# Power_Supply.net
KiCad netlist of a schematic drawn in Altium Designer
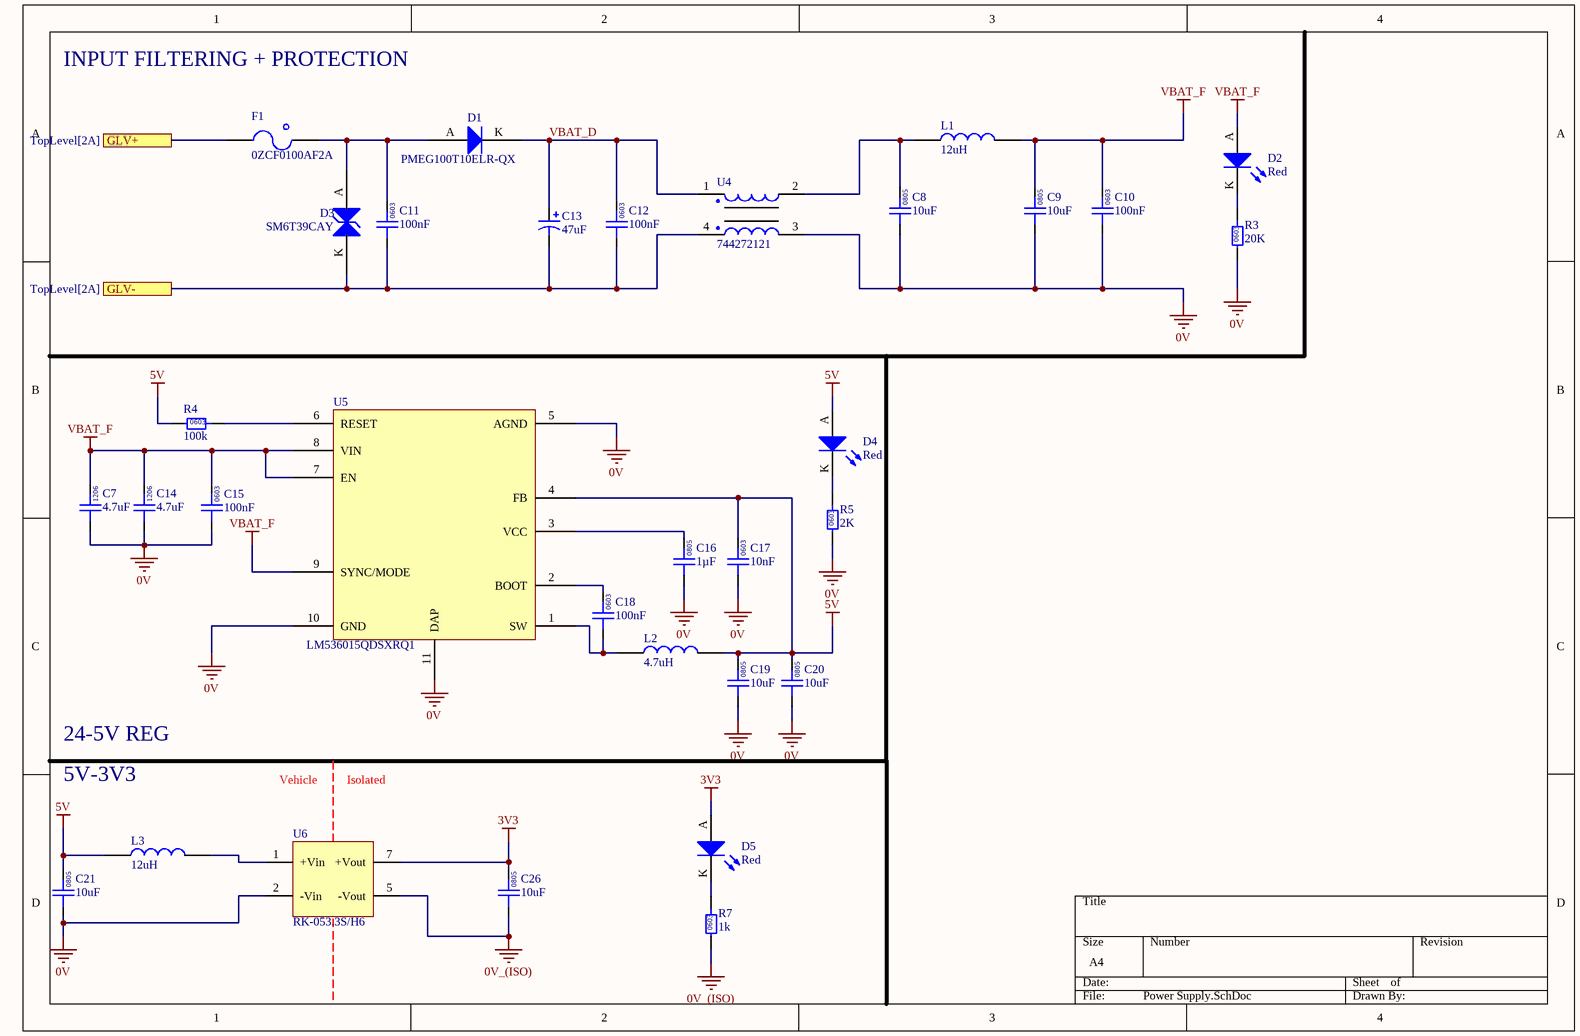
[diagram p0: Power Supply.SchDoc]

(export (version "E")
  (design (tool "Eeschema 10.0.6"))
  (components
    (comp (ref "C7")
      (value "4.7uF")
      (footprint "1206 CAP")
      (fields
        (field (name "PART NUMBER") "GRM31CR71H475KA12K")
        (field (name "MANUFACTURER") "Murata Electronics")
        (field (name "TOLERANCE") "±10%")
      )
      (libsource (lib "ts_standard_library") (part "Capacitor 1206"))
    )
    (comp (ref "C8")
      (value "10uF")
      (footprint "0805")
      (fields
        (field (name "PART NUMBER") "GRM21BR6YA106KE43L")
        (field (name "MANUFACTURER") "muRata")
        (field (name "TOLERANCE") "10%")
      )
      (libsource (lib "ts_standard_library") (part "Capacitor 0805"))
    )
    (comp (ref "C9")
      (value "10uF")
      (footprint "0805")
      (fields
        (field (name "PART NUMBER") "GRM21BR6YA106KE43L")
        (field (name "MANUFACTURER") "muRata")
        (field (name "TOLERANCE") "10%")
      )
      (libsource (lib "ts_standard_library") (part "Capacitor 0805"))
    )
    (comp (ref "C10")
      (value "100nF")
      (footprint "0603")
      (fields
        (field (name "PART NUMBER") "GCM188L81H104KA57D")
        (field (name "MANUFACTURER") "muRata")
        (field (name "TOLERANCE") "±10%")
      )
      (libsource (lib "ts_standard_library") (part "Capacitor 0603"))
    )
    (comp (ref "C11")
      (value "100nF")
      (footprint "0603")
      (fields
        (field (name "PART NUMBER") "GCM188L81H104KA57D")
        (field (name "MANUFACTURER") "muRata")
        (field (name "TOLERANCE") "±10%")
      )
      (libsource (lib "ts_standard_library") (part "Capacitor 0603"))
    )
    (comp (ref "C12")
      (value "100nF")
      (footprint "0603")
      (fields
        (field (name "PART NUMBER") "GCM188L81H104KA57D")
        (field (name "MANUFACTURER") "muRata")
        (field (name "TOLERANCE") "±10%")
      )
      (libsource (lib "ts_standard_library") (part "Capacitor 0603"))
    )
    (comp (ref "C13")
      (value "47uF")
      (footprint "CHEMI-CON ELCO")
      (fields (field (name "PART NUMBER") "HHXA350ARA470MF61G"))
      (libsource (lib "ts_standard_library") (part "Capacitor (Polarised)"))
    )
    (comp (ref "C14")
      (value "4.7uF")
      (footprint "1206 CAP")
      (fields
        (field (name "PART NUMBER") "GRM31CR71H475KA12K")
        (field (name "MANUFACTURER") "Murata Electronics")
        (field (name "TOLERANCE") "±10%")
      )
      (libsource (lib "ts_standard_library") (part "Capacitor 1206"))
    )
    (comp (ref "C15")
      (value "100nF")
      (footprint "0603")
      (fields
        (field (name "PART NUMBER") "GCM188L81H104KA57D")
        (field (name "MANUFACTURER") "muRata")
        (field (name "TOLERANCE") "±10%")
      )
      (libsource (lib "ts_standard_library") (part "Capacitor 0603"))
    )
    (comp (ref "C16")
      (value "1µF")
      (footprint "0805")
      (fields
        (field (name "PART NUMBER") "GCM21BR71H105KA03L")
        (field (name "MANUFACTURER") "muRata")
        (field (name "TOLERANCE") "±10%")
      )
      (libsource (lib "ts_standard_library") (part "Capacitor 0805"))
    )
    (comp (ref "C17")
      (value "10nF")
      (footprint "0603")
      (fields
        (field (name "PART NUMBER") "GCM188L81H103KA03D")
        (field (name "MANUFACTURER") "muRata")
        (field (name "TOLERANCE") "±10%")
      )
      (libsource (lib "ts_standard_library") (part "Capacitor 0603"))
    )
    (comp (ref "C18")
      (value "100nF")
      (footprint "0603")
      (fields
        (field (name "PART NUMBER") "GCM188L81H104KA57D")
        (field (name "MANUFACTURER") "muRata")
        (field (name "TOLERANCE") "±10%")
      )
      (libsource (lib "ts_standard_library") (part "Capacitor 0603"))
    )
    (comp (ref "C19")
      (value "10uF")
      (footprint "0805")
      (fields
        (field (name "PART NUMBER") "GRM21BR6YA106KE43L")
        (field (name "MANUFACTURER") "muRata")
        (field (name "TOLERANCE") "10%")
      )
      (libsource (lib "ts_standard_library") (part "Capacitor 0805"))
    )
    (comp (ref "C20")
      (value "10uF")
      (footprint "0805")
      (fields
        (field (name "PART NUMBER") "GRM21BR6YA106KE43L")
        (field (name "MANUFACTURER") "muRata")
        (field (name "TOLERANCE") "10%")
      )
      (libsource (lib "ts_standard_library") (part "Capacitor 0805"))
    )
    (comp (ref "C21")
      (value "10uF")
      (footprint "0805")
      (fields
        (field (name "PART NUMBER") "GRM21BR6YA106KE43L")
        (field (name "MANUFACTURER") "muRata")
        (field (name "TOLERANCE") "10%")
      )
      (libsource (lib "ts_standard_library") (part "Capacitor 0805"))
    )
    (comp (ref "C26")
      (value "10uF")
      (footprint "0805")
      (fields
        (field (name "PART NUMBER") "GRM21BR6YA106KE43L")
        (field (name "MANUFACTURER") "muRata")
        (field (name "TOLERANCE") "10%")
      )
      (libsource (lib "ts_standard_library") (part "Capacitor 0805"))
    )
    (comp (ref "D1")
      (value "PMEG100T10ELR-QX")
      (footprint "SODFL350X110-2N")
      (description "Diode 100 V 1A Surface Mount SOD-123W")
      (libsource (lib "Team Swinburne") (part "PMEG100T10ELR-QX"))
    )
    (comp (ref "D2")
      (value "Red")
      (footprint "0805 LED")
      (description "Red LED Indication - Discrete 1.75V 0805 (2012 Metric)")
      (fields (field (name "PART NUMBER") "SML-210LTT86") (field (name "MANUFACTURER") "ROHM Semiconductor"))
      (libsource (lib "ts_standard_library") (part "LED"))
    )
    (comp (ref "D3")
      (value "SM6T39CAY")
      (footprint "SM6T39CAY-Footprint-1")
      (description "TVS Diode Single Bi-Dir 33.3V 600W Automotive 2-Pin SMB T/R / TVS DIODE 33.3VWM 69.7VC SMB")
      (libsource (lib "Team Swinburne") (part "SM6T39CAY-Symbol"))
    )
    (comp (ref "D4")
      (value "Red")
      (footprint "0805 LED")
      (description "Red LED Indication - Discrete 1.75V 0805 (2012 Metric)")
      (fields (field (name "PART NUMBER") "SML-210LTT86") (field (name "MANUFACTURER") "ROHM Semiconductor"))
      (libsource (lib "ts_standard_library") (part "LED"))
    )
    (comp (ref "D5")
      (value "Red")
      (footprint "0805 LED")
      (description "Red LED Indication - Discrete 1.75V 0805 (2012 Metric)")
      (fields (field (name "PART NUMBER") "SML-210LTT86") (field (name "MANUFACTURER") "ROHM Semiconductor"))
      (libsource (lib "ts_standard_library") (part "LED"))
    )
    (comp (ref "F1")
      (value "0ZCF0100AF2A")
      (footprint "2920")
      (description "PTC RESET FUSE 60V 1A 292")
      (fields
        (field (name "MANUFACTURER") "Littelfuse Inc.")
        (field (name "DIGIKEY PART NUMBER") "507-2070-1-ND")
      )
      (libsource (lib "ts_standard_library") (part "PTC Fuse"))
    )
    (comp (ref "L1")
      (value "12uH")
      (footprint "1812")
      (fields
        (field (name "PART NUMBER") "RLS-126")
        (field (name "MANUFACTURER") "Recom")
        (field (name "TOLERANCE") "0.2")
      )
      (libsource (lib "ts_standard_library") (part "Inductor"))
    )
    (comp (ref "L2")
      (value "4.7uH")
      (footprint "SRN3015TA-4R7M")
      (fields
        (field (name "PART NUMBER") "SRN4018-4R7M")
        (field (name "MANUFACTURER") "Bourns")
        (field (name "TOLERANCE") "0.2")
      )
      (libsource (lib "ts_standard_library") (part "Inductor"))
    )
    (comp (ref "L3")
      (value "12uH")
      (footprint "1812")
      (fields
        (field (name "PART NUMBER") "RLS-126")
        (field (name "MANUFACTURER") "Recom")
        (field (name "TOLERANCE") "0.2")
      )
      (libsource (lib "ts_standard_library") (part "Inductor"))
    )
    (comp (ref "R3")
      (value "20K")
      (footprint "0603")
      (fields
        (field (name "PART NUMBER") "RC0603FR-0720KL")
        (field (name "MANUFACTURER") "YAGEO")
        (field (name "TOLERANCE") "0.01")
      )
      (libsource (lib "ts_standard_library") (part "Resistor 0603"))
    )
    (comp (ref "R4")
      (value "100k")
      (footprint "0603")
      (fields
        (field (name "PART NUMBER") "RC0603FR-0710KL")
        (field (name "MANUFACTURER") "YAGEO")
        (field (name "TOLERANCE") "0.01")
      )
      (libsource (lib "ts_standard_library") (part "Resistor 0603"))
    )
    (comp (ref "R5")
      (value "2K")
      (footprint "0603")
      (fields
        (field (name "PART NUMBER") "RC0603FR-072KL")
        (field (name "MANUFACTURER") "YAGEO")
        (field (name "TOLERANCE") "0.01")
      )
      (libsource (lib "ts_standard_library") (part "Resistor 0603"))
    )
    (comp (ref "R7")
      (value "1k")
      (footprint "0603")
      (fields
        (field (name "PART NUMBER") "RC0603FR-071KL")
        (field (name "MANUFACTURER") "YAGEO")
        (field (name "TOLERANCE") "0.01")
      )
      (libsource (lib "ts_standard_library") (part "Resistor 0603"))
    )
    (comp (ref "U4")
      (value "744272121")
      (footprint "Wurth 4-PC Pad")
      (fields
        (field (name "MANUFACTURER") "Wurth Electronics Inc")
        (field (name "DIGIKEY PART NUMBER") "732-1489-1-ND")
      )
      (libsource (lib "ts_standard_library") (part "CM Choke"))
    )
    (comp (ref "U5")
      (value "LM536015QDSXRQ1")
      (footprint "TI_10_WSON")
      (description "DC DC CONVERTER 5V")
      (fields
        (field (name "MANUFACTURER") "Texas Instruments")
        (field (name "DIGIKEY PART NUMBER") "296-50359-1-ND")
      )
      (libsource (lib "ts_standard_library") (part "LM536015QDSXRQ1"))
    )
    (comp (ref "U6")
      (value "RK-053.3S/H6")
      (footprint "RK-053.3S/H6")
      (description "DC DC CONVERTER 3.3V 1W")
      (fields (field (name "MANUFACTURER") "Recom"))
      (libsource (lib "ts_standard_library") (part "RK-053.3S/H6"))
    )
  )
  (nets
    (net (code "1") (name "/GLV+") (class "Default")
      (node (ref "F1") (pin "1") (pinfunction "1_1") (pintype "passive"))
    )
    (net (code "2") (name "/GLV-") (class "Default")
      (node (ref "C11") (pin "1") (pinfunction "1_1") (pintype "passive"))
      (node (ref "C12") (pin "1") (pinfunction "1_1") (pintype "passive"))
      (node (ref "C13") (pin "1") (pinfunction "1_1") (pintype "passive"))
      (node (ref "D3") (pin "K") (pintype "passive"))
      (node (ref "U4") (pin "4") (pinfunction "4_4") (pintype "passive"))
    )
    (net (code "3") (name "/VBAT_D") (class "Default")
      (node (ref "C12") (pin "2") (pinfunction "2_2") (pintype "passive"))
      (node (ref "C13") (pin "2") (pinfunction "2_2") (pintype "passive"))
      (node (ref "D1") (pin "K") (pintype "passive"))
      (node (ref "U4") (pin "1") (pinfunction "1_1") (pintype "passive"))
    )
    (net (code "4") (name "0V") (class "Default")
      (node (ref "C10") (pin "1") (pinfunction "1_1") (pintype "passive"))
      (node (ref "C14") (pin "1") (pinfunction "1_1") (pintype "passive"))
      (node (ref "C15") (pin "1") (pinfunction "1_1") (pintype "passive"))
      (node (ref "C16") (pin "1") (pinfunction "1_1") (pintype "passive"))
      (node (ref "C17") (pin "1") (pinfunction "1_1") (pintype "passive"))
      (node (ref "C19") (pin "1") (pinfunction "1_1") (pintype "passive"))
      (node (ref "C20") (pin "1") (pinfunction "1_1") (pintype "passive"))
      (node (ref "C21") (pin "1") (pinfunction "1_1") (pintype "passive"))
      (node (ref "C7") (pin "1") (pinfunction "1_1") (pintype "passive"))
      (node (ref "C8") (pin "1") (pinfunction "1_1") (pintype "passive"))
      (node (ref "C9") (pin "1") (pinfunction "1_1") (pintype "passive"))
      (node (ref "R3") (pin "1") (pinfunction "1_1") (pintype "passive"))
      (node (ref "R5") (pin "1") (pinfunction "1_1") (pintype "passive"))
      (node (ref "U4") (pin "3") (pinfunction "3_3") (pintype "power_in"))
      (node (ref "U5") (pin "10") (pinfunction "GND_10") (pintype "passive"))
      (node (ref "U5") (pin "11") (pinfunction "DAP_11") (pintype "passive"))
      (node (ref "U5") (pin "5") (pinfunction "AGND_5") (pintype "passive"))
      (node (ref "U6") (pin "2") (pinfunction "-Vin_2") (pintype "power_in"))
    )
    (net (code "5") (name "0V_(ISO)") (class "Default")
      (node (ref "C26") (pin "1") (pinfunction "1_1") (pintype "passive"))
      (node (ref "R7") (pin "1") (pinfunction "1_1") (pintype "passive"))
      (node (ref "U6") (pin "5") (pinfunction "-Vout_5") (pintype "power_in"))
    )
    (net (code "6") (name "3V3") (class "Default")
      (node (ref "C26") (pin "2") (pinfunction "2_2") (pintype "passive"))
      (node (ref "D5") (pin "A") (pinfunction "A_A") (pintype "passive"))
      (node (ref "U6") (pin "7") (pinfunction "+Vout_7") (pintype "power_in"))
    )
    (net (code "7") (name "5V") (class "Default")
      (node (ref "C17") (pin "2") (pinfunction "2_2") (pintype "passive"))
      (node (ref "C19") (pin "2") (pinfunction "2_2") (pintype "passive"))
      (node (ref "C20") (pin "2") (pinfunction "2_2") (pintype "passive"))
      (node (ref "C21") (pin "2") (pinfunction "2_2") (pintype "passive"))
      (node (ref "D4") (pin "A") (pinfunction "A_A") (pintype "passive"))
      (node (ref "L2") (pin "1") (pinfunction "1_1") (pintype "passive"))
      (node (ref "L3") (pin "2") (pinfunction "2_2") (pintype "passive"))
      (node (ref "R4") (pin "1") (pinfunction "1_1") (pintype "passive"))
      (node (ref "U5") (pin "4") (pinfunction "FB_4") (pintype "passive"))
    )
    (net (code "8") (name "Net-(C8-Pad2)") (class "Default")
      (node (ref "C8") (pin "2") (pinfunction "2_2") (pintype "passive"))
      (node (ref "L1") (pin "2") (pinfunction "2_2") (pintype "passive"))
      (node (ref "U4") (pin "2") (pinfunction "2_2") (pintype "passive"))
    )
    (net (code "9") (name "Net-(C11-Pad2)") (class "Default")
      (node (ref "C11") (pin "2") (pinfunction "2_2") (pintype "passive"))
      (node (ref "D1") (pin "A") (pintype "passive"))
      (node (ref "D3") (pin "A") (pintype "passive"))
      (node (ref "F1") (pin "2") (pinfunction "2_2") (pintype "passive"))
    )
    (net (code "10") (name "Net-(D2-PadK)") (class "Default")
      (node (ref "D2") (pin "K") (pinfunction "K_K") (pintype "passive"))
      (node (ref "R3") (pin "2") (pinfunction "2_2") (pintype "passive"))
    )
    (net (code "11") (name "Net-(D4-PadK)") (class "Default")
      (node (ref "D4") (pin "K") (pinfunction "K_K") (pintype "passive"))
      (node (ref "R5") (pin "2") (pinfunction "2_2") (pintype "passive"))
    )
    (net (code "12") (name "Net-(D5-PadK)") (class "Default")
      (node (ref "D5") (pin "K") (pinfunction "K_K") (pintype "passive"))
      (node (ref "R7") (pin "2") (pinfunction "2_2") (pintype "passive"))
    )
    (net (code "13") (name "Net-(U5-BOOT)") (class "Default")
      (node (ref "C18") (pin "2") (pinfunction "2_2") (pintype "passive"))
      (node (ref "U5") (pin "2") (pinfunction "BOOT_2") (pintype "passive"))
    )
    (net (code "14") (name "Net-(U5-RESET)") (class "Default")
      (node (ref "R4") (pin "2") (pinfunction "2_2") (pintype "passive"))
      (node (ref "U5") (pin "6") (pinfunction "RESET_6") (pintype "passive"))
    )
    (net (code "15") (name "Net-(U5-SW)") (class "Default")
      (node (ref "C18") (pin "1") (pinfunction "1_1") (pintype "passive"))
      (node (ref "L2") (pin "2") (pinfunction "2_2") (pintype "passive"))
      (node (ref "U5") (pin "1") (pinfunction "SW_1") (pintype "passive"))
    )
    (net (code "16") (name "Net-(U5-VCC)") (class "Default")
      (node (ref "C16") (pin "2") (pinfunction "2_2") (pintype "passive"))
      (node (ref "U5") (pin "3") (pinfunction "VCC_3") (pintype "passive"))
    )
    (net (code "17") (name "Net-(U6-+Vin)") (class "Default")
      (node (ref "L3") (pin "1") (pinfunction "1_1") (pintype "passive"))
      (node (ref "U6") (pin "1") (pinfunction "+Vin_1") (pintype "power_in"))
    )
    (net (code "18") (name "VBAT_F") (class "Default")
      (node (ref "C10") (pin "2") (pinfunction "2_2") (pintype "passive"))
      (node (ref "C14") (pin "2") (pinfunction "2_2") (pintype "passive"))
      (node (ref "C15") (pin "2") (pinfunction "2_2") (pintype "passive"))
      (node (ref "C7") (pin "2") (pinfunction "2_2") (pintype "passive"))
      (node (ref "C9") (pin "2") (pinfunction "2_2") (pintype "passive"))
      (node (ref "D2") (pin "A") (pinfunction "A_A") (pintype "passive"))
      (node (ref "L1") (pin "1") (pinfunction "1_1") (pintype "passive"))
      (node (ref "U5") (pin "7") (pinfunction "EN_7") (pintype "passive"))
      (node (ref "U5") (pin "8") (pinfunction "VIN_8") (pintype "passive"))
      (node (ref "U5") (pin "9") (pinfunction "SYNC/MODE_9") (pintype "passive"))
    )
  )
)
